# SpeedoMetr.net
KiCad netlist of a schematic drawn in Altium Designer
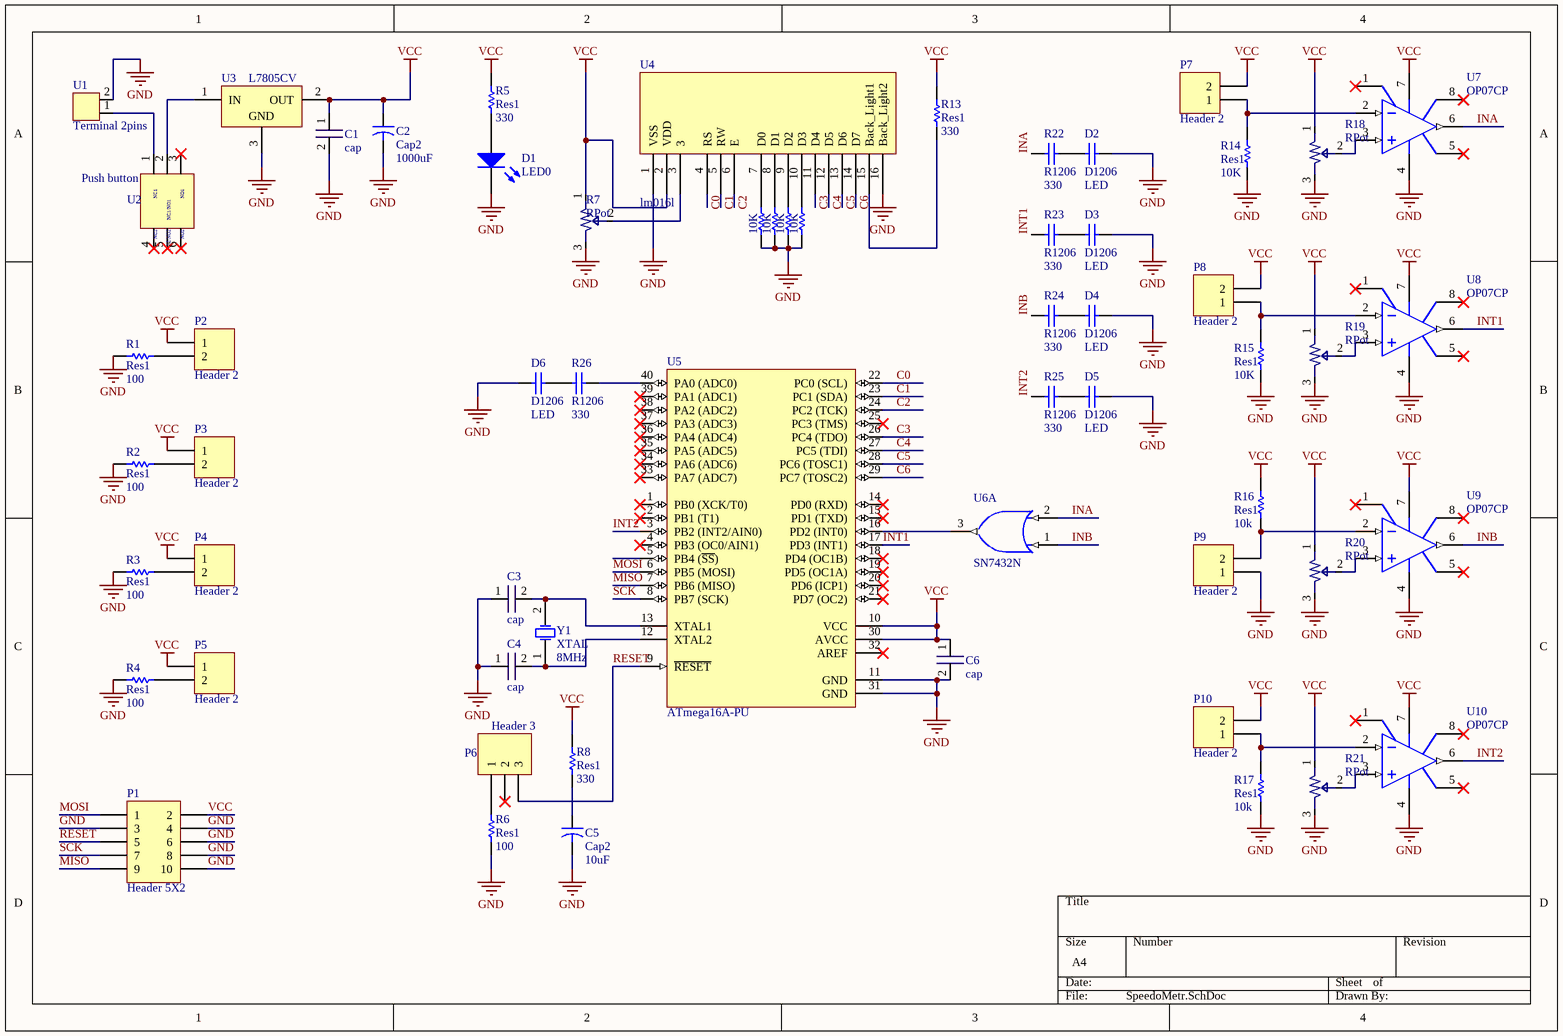
[diagram p0: SpeedoMetr.SchDoc]

(export (version "E")
  (design (tool "Eeschema 10.0.6"))
  (components
    (comp (ref "C1") (value "cap") (footprint "cap 104") (libsource (lib "cap 104") (part "cap 104")))
    (comp (ref "C2")
      (value "Cap2")
      (footprint "RB")
      (description "Capacitor")
      (fields (field (name "ALTIUM_VALUE") "1000uF") (field (name "PUBLISHER") "Altium Limited"))
      (libsource (lib "Miscellaneous Devices") (part "Cap2"))
    )
    (comp (ref "C3") (value "cap") (footprint "cap 104") (libsource (lib "cap 104") (part "cap 104")))
    (comp (ref "C4") (value "cap") (footprint "cap 104") (libsource (lib "cap 104") (part "cap 104")))
    (comp (ref "C5")
      (value "Cap2")
      (footprint "CAPPR5-5x5")
      (description "Capacitor")
      (fields (field (name "ALTIUM_VALUE") "10uF") (field (name "PUBLISHER") "Altium Limited"))
      (libsource (lib "Miscellaneous Devices") (part "Cap2"))
    )
    (comp (ref "C6") (value "cap") (footprint "cap 104") (libsource (lib "cap 104") (part "cap 104")))
    (comp (ref "D1")
      (value "LED0")
      (footprint "LED-0")
      (description "Typical INFRARED GaAs LED")
      (fields (field (name "PUBLISHER") "Altium Limited"))
      (libsource (lib "Miscellaneous Devices") (part "LED0"))
    )
    (comp (ref "D2")
      (value "D1206")
      (footprint "1206")
      (description "Ceramic Chip Capacitor - Standard")
      (fields (field (name "ALTIUM_VALUE") "LED") (field (name "PUBLISHER") "Altium Limited"))
      (libsource (lib "KEMET Chip Capacitor") (part "C1206"))
    )
    (comp (ref "D3")
      (value "D1206")
      (footprint "1206")
      (description "Ceramic Chip Capacitor - Standard")
      (fields (field (name "ALTIUM_VALUE") "LED") (field (name "PUBLISHER") "Altium Limited"))
      (libsource (lib "KEMET Chip Capacitor") (part "C1206"))
    )
    (comp (ref "D4")
      (value "D1206")
      (footprint "1206")
      (description "Ceramic Chip Capacitor - Standard")
      (fields (field (name "ALTIUM_VALUE") "LED") (field (name "PUBLISHER") "Altium Limited"))
      (libsource (lib "KEMET Chip Capacitor") (part "C1206"))
    )
    (comp (ref "D5")
      (value "D1206")
      (footprint "1206")
      (description "Ceramic Chip Capacitor - Standard")
      (fields (field (name "ALTIUM_VALUE") "LED") (field (name "PUBLISHER") "Altium Limited"))
      (libsource (lib "KEMET Chip Capacitor") (part "C1206"))
    )
    (comp (ref "D6")
      (value "D1206")
      (footprint "1206")
      (description "Ceramic Chip Capacitor - Standard")
      (fields (field (name "ALTIUM_VALUE") "LED") (field (name "PUBLISHER") "Altium Limited"))
      (libsource (lib "KEMET Chip Capacitor") (part "C1206"))
    )
    (comp (ref "P1")
      (value "Header 5X2")
      (footprint "HDR2X5")
      (description "Header, 5-Pin, Dual row")
      (fields (field (name "PUBLISHER") "Altium Limited"))
      (libsource (lib "Miscellaneous Connectors") (part "Header 5X2"))
    )
    (comp (ref "P2")
      (value "Header 2")
      (footprint "HDR1X2")
      (description "Header, 2-Pin")
      (fields (field (name "PUBLISHER") "Altium Limited"))
      (libsource (lib "") (part "Header 2_1"))
    )
    (comp (ref "P3")
      (value "Header 2")
      (footprint "HDR1X2")
      (description "Header, 2-Pin")
      (fields (field (name "PUBLISHER") "Altium Limited"))
      (libsource (lib "") (part "Header 2_1"))
    )
    (comp (ref "P4")
      (value "Header 2")
      (footprint "HDR1X2")
      (description "Header, 2-Pin")
      (fields (field (name "PUBLISHER") "Altium Limited"))
      (libsource (lib "") (part "Header 2_1"))
    )
    (comp (ref "P5")
      (value "Header 2")
      (footprint "HDR1X2")
      (description "Header, 2-Pin")
      (fields (field (name "PUBLISHER") "Altium Limited"))
      (libsource (lib "") (part "Header 2_1"))
    )
    (comp (ref "P6")
      (value "Header 3")
      (footprint "HDR1X3")
      (description "Header, 3-Pin")
      (fields (field (name "PUBLISHER") "Altium Limited"))
      (libsource (lib "Miscellaneous Connectors") (part "Header 3"))
    )
    (comp (ref "P7")
      (value "Header 2")
      (footprint "HDR1X2")
      (description "Header, 2-Pin")
      (fields (field (name "PUBLISHER") "Altium Limited"))
      (libsource (lib "Miscellaneous Connectors") (part "Header 2"))
    )
    (comp (ref "P8")
      (value "Header 2")
      (footprint "HDR1X2")
      (description "Header, 2-Pin")
      (fields (field (name "PUBLISHER") "Altium Limited"))
      (libsource (lib "Miscellaneous Connectors") (part "Header 2"))
    )
    (comp (ref "P9")
      (value "Header 2")
      (footprint "HDR1X2")
      (description "Header, 2-Pin")
      (fields (field (name "PUBLISHER") "Altium Limited"))
      (libsource (lib "Miscellaneous Connectors") (part "Header 2"))
    )
    (comp (ref "P10")
      (value "Header 2")
      (footprint "HDR1X2")
      (description "Header, 2-Pin")
      (fields (field (name "PUBLISHER") "Altium Limited"))
      (libsource (lib "Miscellaneous Connectors") (part "Header 2"))
    )
    (comp (ref "R1")
      (value "Res1")
      (footprint "AXIAL-0.3")
      (description "Resistor")
      (fields (field (name "ALTIUM_VALUE") "100") (field (name "PUBLISHER") "Altium Limited"))
      (libsource (lib "Miscellaneous Devices") (part "Res1"))
    )
    (comp (ref "R2")
      (value "Res1")
      (footprint "AXIAL-0.3")
      (description "Resistor")
      (fields (field (name "ALTIUM_VALUE") "100") (field (name "PUBLISHER") "Altium Limited"))
      (libsource (lib "Miscellaneous Devices") (part "Res1"))
    )
    (comp (ref "R3")
      (value "Res1")
      (footprint "AXIAL-0.3")
      (description "Resistor")
      (fields (field (name "ALTIUM_VALUE") "100") (field (name "PUBLISHER") "Altium Limited"))
      (libsource (lib "Miscellaneous Devices") (part "Res1"))
    )
    (comp (ref "R4")
      (value "Res1")
      (footprint "AXIAL-0.3")
      (description "Resistor")
      (fields (field (name "ALTIUM_VALUE") "100") (field (name "PUBLISHER") "Altium Limited"))
      (libsource (lib "Miscellaneous Devices") (part "Res1"))
    )
    (comp (ref "R5")
      (value "Res1")
      (footprint "AXIAL-0.3")
      (description "Resistor")
      (fields (field (name "ALTIUM_VALUE") "330") (field (name "PUBLISHER") "Altium Limited"))
      (libsource (lib "Miscellaneous Devices") (part "Res1"))
    )
    (comp (ref "R6")
      (value "Res1")
      (footprint "AXIAL-0.3")
      (description "Resistor")
      (fields (field (name "ALTIUM_VALUE") "100") (field (name "PUBLISHER") "Altium Limited"))
      (libsource (lib "Miscellaneous Devices") (part "Res1"))
    )
    (comp (ref "R7")
      (value "RPot")
      (footprint "PCBComponent_1")
      (description "Potentiometer")
      (libsource (lib "POT-Blue") (part "Component_1"))
    )
    (comp (ref "R8")
      (value "Res1")
      (footprint "AXIAL-0.3")
      (description "Resistor")
      (fields (field (name "ALTIUM_VALUE") "330") (field (name "PUBLISHER") "Altium Limited"))
      (libsource (lib "Miscellaneous Devices") (part "Res1"))
    )
    (comp (ref "R9")
      (value "10K")
      (footprint "AXIAL-0.3")
      (description "Resistor")
      (fields (field (name "Comment") "Res1") (field (name "PUBLISHER") "Altium Limited"))
      (libsource (lib "Miscellaneous Devices") (part "Res1"))
    )
    (comp (ref "R10")
      (value "10K")
      (footprint "AXIAL-0.3")
      (description "Resistor")
      (fields (field (name "Comment") "Res1") (field (name "PUBLISHER") "Altium Limited"))
      (libsource (lib "Miscellaneous Devices") (part "Res1"))
    )
    (comp (ref "R11")
      (value "10K")
      (footprint "AXIAL-0.3")
      (description "Resistor")
      (fields (field (name "Comment") "Res1") (field (name "PUBLISHER") "Altium Limited"))
      (libsource (lib "Miscellaneous Devices") (part "Res1"))
    )
    (comp (ref "R12")
      (value "10K")
      (footprint "AXIAL-0.3")
      (description "Resistor")
      (fields (field (name "Comment") "Res1") (field (name "PUBLISHER") "Altium Limited"))
      (libsource (lib "Miscellaneous Devices") (part "Res1"))
    )
    (comp (ref "R13")
      (value "Res1")
      (footprint "AXIAL-0.3")
      (description "Resistor")
      (fields (field (name "ALTIUM_VALUE") "330") (field (name "PUBLISHER") "Altium Limited"))
      (libsource (lib "Miscellaneous Devices") (part "Res1"))
    )
    (comp (ref "R14")
      (value "Res1")
      (footprint "AXIAL-0.3")
      (description "Resistor")
      (fields (field (name "ALTIUM_VALUE") "10K") (field (name "PUBLISHER") "Altium Limited"))
      (libsource (lib "Miscellaneous Devices") (part "Res1"))
    )
    (comp (ref "R15")
      (value "Res1")
      (footprint "AXIAL-0.3")
      (description "Resistor")
      (fields (field (name "ALTIUM_VALUE") "10K") (field (name "PUBLISHER") "Altium Limited"))
      (libsource (lib "Miscellaneous Devices") (part "Res1"))
    )
    (comp (ref "R16")
      (value "Res1")
      (footprint "AXIAL-0.3")
      (description "Resistor")
      (fields (field (name "ALTIUM_VALUE") "10k") (field (name "PUBLISHER") "Altium Limited"))
      (libsource (lib "Miscellaneous Devices") (part "Res1"))
    )
    (comp (ref "R17")
      (value "Res1")
      (footprint "AXIAL-0.3")
      (description "Resistor")
      (fields (field (name "ALTIUM_VALUE") "10k") (field (name "PUBLISHER") "Altium Limited"))
      (libsource (lib "Miscellaneous Devices") (part "Res1"))
    )
    (comp (ref "R18")
      (value "RPot")
      (footprint "PCBComponent_1")
      (description "Potentiometer")
      (libsource (lib "POT-Blue") (part "Component_1"))
    )
    (comp (ref "R19")
      (value "RPot")
      (footprint "PCBComponent_1")
      (description "Potentiometer")
      (libsource (lib "POT-Blue") (part "Component_1"))
    )
    (comp (ref "R20")
      (value "RPot")
      (footprint "PCBComponent_1")
      (description "Potentiometer")
      (libsource (lib "POT-Blue") (part "Component_1"))
    )
    (comp (ref "R21")
      (value "RPot")
      (footprint "PCBComponent_1")
      (description "Potentiometer")
      (libsource (lib "POT-Blue") (part "Component_1"))
    )
    (comp (ref "R22")
      (value "R1206")
      (footprint "1206")
      (description "Ceramic Chip Capacitor - Standard")
      (fields (field (name "ALTIUM_VALUE") "330") (field (name "PUBLISHER") "Altium Limited"))
      (libsource (lib "KEMET Chip Capacitor") (part "C1206"))
    )
    (comp (ref "R23")
      (value "R1206")
      (footprint "1206")
      (description "Ceramic Chip Capacitor - Standard")
      (fields (field (name "ALTIUM_VALUE") "330") (field (name "PUBLISHER") "Altium Limited"))
      (libsource (lib "KEMET Chip Capacitor") (part "C1206"))
    )
    (comp (ref "R24")
      (value "R1206")
      (footprint "1206")
      (description "Ceramic Chip Capacitor - Standard")
      (fields (field (name "ALTIUM_VALUE") "330") (field (name "PUBLISHER") "Altium Limited"))
      (libsource (lib "KEMET Chip Capacitor") (part "C1206"))
    )
    (comp (ref "R25")
      (value "R1206")
      (footprint "1206")
      (description "Ceramic Chip Capacitor - Standard")
      (fields (field (name "ALTIUM_VALUE") "330") (field (name "PUBLISHER") "Altium Limited"))
      (libsource (lib "KEMET Chip Capacitor") (part "C1206"))
    )
    (comp (ref "R26")
      (value "R1206")
      (footprint "1206")
      (description "Ceramic Chip Capacitor - Standard")
      (fields (field (name "ALTIUM_VALUE") "330") (field (name "PUBLISHER") "Altium Limited"))
      (libsource (lib "KEMET Chip Capacitor") (part "C1206"))
    )
    (comp (ref "U1")
      (value "Terminal 2pins")
      (footprint "Terminal 2pins")
      (libsource (lib "Terminal 2pins") (part "Terminal"))
    )
    (comp (ref "U2")
      (value "Push button")
      (footprint "PCBComponent_1")
      (description "button")
      (libsource (lib "Push button 6 pin") (part "Component_1"))
    )
    (comp (ref "U3")
      (value "L7805CV")
      (footprint "TO220ABN")
      (description "Positive Voltage Regulator")
      (fields (field (name "PUBLISHER") "Altium Limited"))
      (libsource (lib "ST Power Mgt Voltage Regulator") (part "L7805CV"))
    )
    (comp (ref "U4")
      (value "lm016l")
      (footprint "PCBComponent_1")
      (description "LCD display")
      (libsource (lib "LCD16x2") (part "lm016l"))
    )
    (comp (ref "U5")
      (value "ATmega16A-PU")
      (footprint "40P6")
      (fields (field (name "PUBLISHER") "Altium Limited"))
      (libsource (lib "Atmel Microcontroller 8-Bit megaAVR") (part "ATmega16A-PU"))
    )
    (comp (ref "U6")
      (value "SN7432N")
      (footprint "N014")
      (description "Quadruple 2-Input Positive-OR Gate")
      (fields (field (name "PUBLISHER") "Altium Limited"))
      (libsource (lib "TI Logic Gate 1") (part "SN7432N"))
    )
    (comp (ref "U7")
      (value "OP07CP")
      (footprint "N-8_A")
      (description "Ultra-Low Offset Voltage Operational Amplifier")
      (fields (field (name "PUBLISHER") "Altium Limited"))
      (libsource (lib "AD Operational Amplifier") (part "OP07CP"))
    )
    (comp (ref "U8")
      (value "OP07CP")
      (footprint "N-8_A")
      (description "Ultra-Low Offset Voltage Operational Amplifier")
      (fields (field (name "PUBLISHER") "Altium Limited"))
      (libsource (lib "AD Operational Amplifier") (part "OP07CP"))
    )
    (comp (ref "U9")
      (value "OP07CP")
      (footprint "N-8_A")
      (description "Ultra-Low Offset Voltage Operational Amplifier")
      (fields (field (name "PUBLISHER") "Altium Limited"))
      (libsource (lib "AD Operational Amplifier") (part "OP07CP"))
    )
    (comp (ref "U10")
      (value "OP07CP")
      (footprint "N-8_A")
      (description "Ultra-Low Offset Voltage Operational Amplifier")
      (fields (field (name "PUBLISHER") "Altium Limited"))
      (libsource (lib "AD Operational Amplifier") (part "OP07CP"))
    )
    (comp (ref "Y1")
      (value "XTAL")
      (footprint "XTAL")
      (description "Crystal Oscillator")
      (fields
        (field (name "ALTIUM_VALUE") "8MHz")
        (field (name "DESIGNER") "Meysam Parvizi")
        (field (name "EMAIL") "meysam.parvizi.ir@gmail.com")
      )
      (libsource (lib "mp") (part "XTAL"))
    )
  )
  (nets
    (net (code "1") (name "/C0") (class "Default")
      (node (ref "U4") (pin "4") (pinfunction "RS_4") (pintype "passive"))
      (node (ref "U5") (pin "22") (pinfunction "PC0_(SCL)_22") (pintype "bidirectional"))
    )
    (net (code "2") (name "/C1") (class "Default")
      (node (ref "U4") (pin "5") (pinfunction "RW_5") (pintype "passive"))
      (node (ref "U5") (pin "23") (pinfunction "PC1_(SDA)_23") (pintype "bidirectional"))
    )
    (net (code "3") (name "/C2") (class "Default")
      (node (ref "U4") (pin "6") (pinfunction "E_6") (pintype "passive"))
      (node (ref "U5") (pin "24") (pinfunction "PC2_(TCK)_24") (pintype "bidirectional"))
    )
    (net (code "4") (name "/C3") (class "Default")
      (node (ref "U4") (pin "11") (pinfunction "D4_11") (pintype "passive"))
      (node (ref "U5") (pin "26") (pinfunction "PC4_(TDO)_26") (pintype "bidirectional"))
    )
    (net (code "5") (name "/C4") (class "Default")
      (node (ref "U4") (pin "12") (pinfunction "D5_12") (pintype "passive"))
      (node (ref "U5") (pin "27") (pinfunction "PC5_(TDI)_27") (pintype "bidirectional"))
    )
    (net (code "6") (name "/C5") (class "Default")
      (node (ref "U4") (pin "13") (pinfunction "D6_13") (pintype "passive"))
      (node (ref "U5") (pin "28") (pinfunction "PC6_(TOSC1)_28") (pintype "bidirectional"))
    )
    (net (code "7") (name "/C6") (class "Default")
      (node (ref "U4") (pin "14") (pinfunction "D7_14") (pintype "passive"))
      (node (ref "U5") (pin "29") (pinfunction "PC7_(TOSC2)_29") (pintype "bidirectional"))
    )
    (net (code "8") (name "/INA") (class "Default")
      (node (ref "R22") (pin "1") (pinfunction "1_1") (pintype "passive"))
      (node (ref "U6") (pin "2") (pinfunction "B_2") (pintype "input"))
      (node (ref "U7") (pin "6") (pinfunction "OUT_6") (pintype "output"))
    )
    (net (code "9") (name "/INB") (class "Default")
      (node (ref "R24") (pin "1") (pinfunction "1_1") (pintype "passive"))
      (node (ref "U6") (pin "1") (pinfunction "A_1") (pintype "input"))
      (node (ref "U9") (pin "6") (pinfunction "OUT_6") (pintype "output"))
    )
    (net (code "10") (name "/INT1") (class "Default")
      (node (ref "R23") (pin "1") (pinfunction "1_1") (pintype "passive"))
      (node (ref "U5") (pin "17") (pinfunction "PD3_(INT1)_17") (pintype "bidirectional"))
      (node (ref "U8") (pin "6") (pinfunction "OUT_6") (pintype "output"))
    )
    (net (code "11") (name "/INT2") (class "Default")
      (node (ref "R25") (pin "1") (pinfunction "1_1") (pintype "passive"))
      (node (ref "U10") (pin "6") (pinfunction "OUT_6") (pintype "output"))
      (node (ref "U5") (pin "3") (pinfunction "PB2_(INT2/AIN0)_3") (pintype "bidirectional"))
    )
    (net (code "12") (name "/MISO") (class "Default")
      (node (ref "P1") (pin "9") (pinfunction "9_9") (pintype "passive"))
      (node (ref "U5") (pin "7") (pinfunction "PB6_(MISO)_7") (pintype "bidirectional"))
    )
    (net (code "13") (name "/MOSI") (class "Default")
      (node (ref "P1") (pin "1") (pinfunction "1_1") (pintype "passive"))
      (node (ref "U5") (pin "6") (pinfunction "PB5_(MOSI)_6") (pintype "bidirectional"))
    )
    (net (code "14") (name "/RESET") (class "Default")
      (node (ref "P1") (pin "5") (pinfunction "5_5") (pintype "passive"))
      (node (ref "P6") (pin "3") (pinfunction "3_3") (pintype "passive"))
      (node (ref "U5") (pin "9") (pinfunction "~{RESET}_9") (pintype "input"))
    )
    (net (code "15") (name "/SCK") (class "Default")
      (node (ref "P1") (pin "7") (pinfunction "7_7") (pintype "passive"))
      (node (ref "U5") (pin "8") (pinfunction "PB7_(SCK)_8") (pintype "bidirectional"))
    )
    (net (code "16") (name "GND") (class "Default")
      (node (ref "C1") (pin "2") (pinfunction "2_2") (pintype "passive"))
      (node (ref "C2") (pin "2") (pinfunction "2_2") (pintype "passive"))
      (node (ref "C3") (pin "1") (pinfunction "1_1") (pintype "passive"))
      (node (ref "C4") (pin "1") (pinfunction "1_1") (pintype "passive"))
      (node (ref "C5") (pin "2") (pinfunction "2_2") (pintype "passive"))
      (node (ref "C6") (pin "2") (pinfunction "2_2") (pintype "passive"))
      (node (ref "D1") (pin "2") (pinfunction "K_2") (pintype "passive"))
      (node (ref "D2") (pin "2") (pinfunction "2_2") (pintype "passive"))
      (node (ref "D3") (pin "2") (pinfunction "2_2") (pintype "passive"))
      (node (ref "D4") (pin "2") (pinfunction "2_2") (pintype "passive"))
      (node (ref "D5") (pin "2") (pinfunction "2_2") (pintype "passive"))
      (node (ref "D6") (pin "2") (pinfunction "2_2") (pintype "passive"))
      (node (ref "P1") (pin "10") (pinfunction "10_10") (pintype "passive"))
      (node (ref "P1") (pin "3") (pinfunction "3_3") (pintype "passive"))
      (node (ref "P1") (pin "4") (pinfunction "4_4") (pintype "passive"))
      (node (ref "P1") (pin "6") (pinfunction "6_6") (pintype "passive"))
      (node (ref "P1") (pin "8") (pinfunction "8_8") (pintype "passive"))
      (node (ref "P9") (pin "1") (pinfunction "1_1") (pintype "passive"))
      (node (ref "R1") (pin "1") (pinfunction "1_1") (pintype "passive"))
      (node (ref "R10") (pin "1") (pinfunction "1_1") (pintype "passive"))
      (node (ref "R11") (pin "1") (pinfunction "1_1") (pintype "passive"))
      (node (ref "R12") (pin "1") (pinfunction "1_1") (pintype "passive"))
      (node (ref "R14") (pin "1") (pinfunction "1_1") (pintype "passive"))
      (node (ref "R15") (pin "1") (pinfunction "1_1") (pintype "passive"))
      (node (ref "R17") (pin "1") (pinfunction "1_1") (pintype "passive"))
      (node (ref "R18") (pin "3") (pinfunction "3_3") (pintype "passive"))
      (node (ref "R19") (pin "3") (pinfunction "3_3") (pintype "passive"))
      (node (ref "R2") (pin "1") (pinfunction "1_1") (pintype "passive"))
      (node (ref "R20") (pin "3") (pinfunction "3_3") (pintype "passive"))
      (node (ref "R21") (pin "3") (pinfunction "3_3") (pintype "passive"))
      (node (ref "R3") (pin "1") (pinfunction "1_1") (pintype "passive"))
      (node (ref "R4") (pin "1") (pinfunction "1_1") (pintype "passive"))
      (node (ref "R6") (pin "1") (pinfunction "1_1") (pintype "passive"))
      (node (ref "R7") (pin "3") (pinfunction "3_3") (pintype "passive"))
      (node (ref "R9") (pin "1") (pinfunction "1_1") (pintype "passive"))
      (node (ref "U1") (pin "2") (pinfunction "2_2") (pintype "passive"))
      (node (ref "U10") (pin "4") (pinfunction "V-_4") (pintype "power_in"))
      (node (ref "U3") (pin "3") (pinfunction "GND_3") (pintype "power_in"))
      (node (ref "U4") (pin "1") (pinfunction "VSS_1") (pintype "passive"))
      (node (ref "U4") (pin "16") (pinfunction "Back_Light2_16") (pintype "passive"))
      (node (ref "U5") (pin "11") (pinfunction "GND_11") (pintype "power_in"))
      (node (ref "U5") (pin "31") (pinfunction "GND_31") (pintype "power_in"))
      (node (ref "U6") (pin "7") (pinfunction "GND_7") (pintype "power_in"))
      (node (ref "U7") (pin "4") (pinfunction "V-_4") (pintype "power_in"))
      (node (ref "U8") (pin "4") (pinfunction "V-_4") (pintype "power_in"))
      (node (ref "U9") (pin "4") (pinfunction "V-_4") (pintype "power_in"))
    )
    (net (code "17") (name "Net-(C5-Pad1)") (class "Default")
      (node (ref "C5") (pin "1") (pinfunction "1_1") (pintype "passive"))
      (node (ref "R8") (pin "1") (pinfunction "1_1") (pintype "passive"))
    )
    (net (code "18") (name "Net-(D1-A)") (class "Default")
      (node (ref "D1") (pin "1") (pinfunction "A_1") (pintype "passive"))
      (node (ref "R5") (pin "2") (pinfunction "2_2") (pintype "passive"))
    )
    (net (code "19") (name "Net-(D2-Pad1)") (class "Default")
      (node (ref "D2") (pin "1") (pinfunction "1_1") (pintype "passive"))
      (node (ref "R22") (pin "2") (pinfunction "2_2") (pintype "passive"))
    )
    (net (code "20") (name "Net-(D3-Pad1)") (class "Default")
      (node (ref "D3") (pin "1") (pinfunction "1_1") (pintype "passive"))
      (node (ref "R23") (pin "2") (pinfunction "2_2") (pintype "passive"))
    )
    (net (code "21") (name "Net-(D4-Pad1)") (class "Default")
      (node (ref "D4") (pin "1") (pinfunction "1_1") (pintype "passive"))
      (node (ref "R24") (pin "2") (pinfunction "2_2") (pintype "passive"))
    )
    (net (code "22") (name "Net-(D5-Pad1)") (class "Default")
      (node (ref "D5") (pin "1") (pinfunction "1_1") (pintype "passive"))
      (node (ref "R25") (pin "2") (pinfunction "2_2") (pintype "passive"))
    )
    (net (code "23") (name "Net-(D6-Pad1)") (class "Default")
      (node (ref "D6") (pin "1") (pinfunction "1_1") (pintype "passive"))
      (node (ref "R26") (pin "2") (pinfunction "2_2") (pintype "passive"))
    )
    (net (code "24") (name "Net-(P2-Pad2)") (class "Default")
      (node (ref "P2") (pin "2") (pinfunction "2_2") (pintype "passive"))
      (node (ref "R1") (pin "2") (pinfunction "2_2") (pintype "passive"))
    )
    (net (code "25") (name "Net-(P3-Pad2)") (class "Default")
      (node (ref "P3") (pin "2") (pinfunction "2_2") (pintype "passive"))
      (node (ref "R2") (pin "2") (pinfunction "2_2") (pintype "passive"))
    )
    (net (code "26") (name "Net-(P4-Pad2)") (class "Default")
      (node (ref "P4") (pin "2") (pinfunction "2_2") (pintype "passive"))
      (node (ref "R3") (pin "2") (pinfunction "2_2") (pintype "passive"))
    )
    (net (code "27") (name "Net-(P5-Pad2)") (class "Default")
      (node (ref "P5") (pin "2") (pinfunction "2_2") (pintype "passive"))
      (node (ref "R4") (pin "2") (pinfunction "2_2") (pintype "passive"))
    )
    (net (code "28") (name "Net-(P6-Pad1)") (class "Default")
      (node (ref "P6") (pin "1") (pinfunction "1_1") (pintype "passive"))
      (node (ref "R6") (pin "2") (pinfunction "2_2") (pintype "passive"))
    )
    (net (code "29") (name "Net-(R7-Pad2)") (class "Default")
      (node (ref "R7") (pin "2") (pinfunction "2_2") (pintype "passive"))
      (node (ref "U4") (pin "3") (pinfunction "3_3") (pintype "passive"))
    )
    (net (code "30") (name "Net-(U1-Pad1)") (class "Default")
      (node (ref "U1") (pin "1") (pinfunction "1_1") (pintype "passive"))
      (node (ref "U2") (pin "1") (pinfunction "1_1") (pintype "passive"))
    )
    (net (code "31") (name "Net-(U3-IN)") (class "Default")
      (node (ref "U2") (pin "2") (pinfunction "2_2") (pintype "passive"))
      (node (ref "U3") (pin "1") (pinfunction "IN_1") (pintype "power_in"))
    )
    (net (code "32") (name "Net-(U4-Back_Light1)") (class "Default")
      (node (ref "R13") (pin "2") (pinfunction "2_2") (pintype "passive"))
      (node (ref "U4") (pin "15") (pinfunction "Back_Light1_15") (pintype "passive"))
    )
    (net (code "33") (name "Net-(U4-D0)") (class "Default")
      (node (ref "R9") (pin "2") (pinfunction "2_2") (pintype "passive"))
      (node (ref "U4") (pin "7") (pinfunction "D0_7") (pintype "passive"))
    )
    (net (code "34") (name "Net-(U4-D1)") (class "Default")
      (node (ref "R10") (pin "2") (pinfunction "2_2") (pintype "passive"))
      (node (ref "U4") (pin "8") (pinfunction "D1_8") (pintype "passive"))
    )
    (net (code "35") (name "Net-(U4-D2)") (class "Default")
      (node (ref "R11") (pin "2") (pinfunction "2_2") (pintype "passive"))
      (node (ref "U4") (pin "9") (pinfunction "D2_9") (pintype "passive"))
    )
    (net (code "36") (name "Net-(U4-D3)") (class "Default")
      (node (ref "R12") (pin "2") (pinfunction "2_2") (pintype "passive"))
      (node (ref "U4") (pin "10") (pinfunction "D3_10") (pintype "passive"))
    )
    (net (code "37") (name "Net-(U5-PA0_(ADC0))") (class "Default")
      (node (ref "R26") (pin "1") (pinfunction "1_1") (pintype "passive"))
      (node (ref "U5") (pin "40") (pinfunction "PA0_(ADC0)_40") (pintype "bidirectional"))
    )
    (net (code "38") (name "Net-(U5-PD2_(INT0))") (class "Default")
      (node (ref "U5") (pin "16") (pinfunction "PD2_(INT0)_16") (pintype "bidirectional"))
      (node (ref "U6") (pin "3") (pinfunction "Y_3") (pintype "output"))
    )
    (net (code "39") (name "Net-(U5-XTAL1)") (class "Default")
      (node (ref "C3") (pin "2") (pinfunction "2_2") (pintype "passive"))
      (node (ref "U5") (pin "13") (pinfunction "XTAL1_13") (pintype "passive"))
      (node (ref "Y1") (pin "2") (pinfunction "OSC2_2") (pintype "passive"))
    )
    (net (code "40") (name "Net-(U5-XTAL2)") (class "Default")
      (node (ref "C4") (pin "2") (pinfunction "2_2") (pintype "passive"))
      (node (ref "U5") (pin "12") (pinfunction "XTAL2_12") (pintype "passive"))
      (node (ref "Y1") (pin "1") (pinfunction "OSC1_1") (pintype "passive"))
    )
    (net (code "41") (name "Net-(U7-IN+)") (class "Default")
      (node (ref "R18") (pin "2") (pinfunction "2_2") (pintype "passive"))
      (node (ref "U7") (pin "3") (pinfunction "IN+_3") (pintype "input"))
    )
    (net (code "42") (name "Net-(U7-IN-)") (class "Default")
      (node (ref "P7") (pin "1") (pinfunction "1_1") (pintype "passive"))
      (node (ref "R14") (pin "2") (pinfunction "2_2") (pintype "passive"))
      (node (ref "U7") (pin "2") (pinfunction "IN-_2") (pintype "input"))
    )
    (net (code "43") (name "Net-(U8-IN+)") (class "Default")
      (node (ref "R19") (pin "2") (pinfunction "2_2") (pintype "passive"))
      (node (ref "U8") (pin "3") (pinfunction "IN+_3") (pintype "input"))
    )
    (net (code "44") (name "Net-(U8-IN-)") (class "Default")
      (node (ref "P8") (pin "1") (pinfunction "1_1") (pintype "passive"))
      (node (ref "R15") (pin "2") (pinfunction "2_2") (pintype "passive"))
      (node (ref "U8") (pin "2") (pinfunction "IN-_2") (pintype "input"))
    )
    (net (code "45") (name "Net-(U9-IN+)") (class "Default")
      (node (ref "R20") (pin "2") (pinfunction "2_2") (pintype "passive"))
      (node (ref "U9") (pin "3") (pinfunction "IN+_3") (pintype "input"))
    )
    (net (code "46") (name "Net-(U9-IN-)") (class "Default")
      (node (ref "P9") (pin "2") (pinfunction "2_2") (pintype "passive"))
      (node (ref "R16") (pin "1") (pinfunction "1_1") (pintype "passive"))
      (node (ref "U9") (pin "2") (pinfunction "IN-_2") (pintype "input"))
    )
    (net (code "47") (name "Net-(U10-IN+)") (class "Default")
      (node (ref "R21") (pin "2") (pinfunction "2_2") (pintype "passive"))
      (node (ref "U10") (pin "3") (pinfunction "IN+_3") (pintype "input"))
    )
    (net (code "48") (name "Net-(U10-IN-)") (class "Default")
      (node (ref "P10") (pin "1") (pinfunction "1_1") (pintype "passive"))
      (node (ref "R17") (pin "2") (pinfunction "2_2") (pintype "passive"))
      (node (ref "U10") (pin "2") (pinfunction "IN-_2") (pintype "input"))
    )
    (net (code "49") (name "VCC") (class "Default")
      (node (ref "C1") (pin "1") (pinfunction "1_1") (pintype "passive"))
      (node (ref "C2") (pin "1") (pinfunction "1_1") (pintype "passive"))
      (node (ref "C6") (pin "1") (pinfunction "1_1") (pintype "passive"))
      (node (ref "P1") (pin "2") (pinfunction "2_2") (pintype "passive"))
      (node (ref "P10") (pin "2") (pinfunction "2_2") (pintype "passive"))
      (node (ref "P2") (pin "1") (pinfunction "1_1") (pintype "passive"))
      (node (ref "P3") (pin "1") (pinfunction "1_1") (pintype "passive"))
      (node (ref "P4") (pin "1") (pinfunction "1_1") (pintype "passive"))
      (node (ref "P5") (pin "1") (pinfunction "1_1") (pintype "passive"))
      (node (ref "P7") (pin "2") (pinfunction "2_2") (pintype "passive"))
      (node (ref "P8") (pin "2") (pinfunction "2_2") (pintype "passive"))
      (node (ref "R13") (pin "1") (pinfunction "1_1") (pintype "passive"))
      (node (ref "R16") (pin "2") (pinfunction "2_2") (pintype "passive"))
      (node (ref "R18") (pin "1") (pinfunction "1_1") (pintype "passive"))
      (node (ref "R19") (pin "1") (pinfunction "1_1") (pintype "passive"))
      (node (ref "R20") (pin "1") (pinfunction "1_1") (pintype "passive"))
      (node (ref "R21") (pin "1") (pinfunction "1_1") (pintype "passive"))
      (node (ref "R5") (pin "1") (pinfunction "1_1") (pintype "passive"))
      (node (ref "R7") (pin "1") (pinfunction "1_1") (pintype "passive"))
      (node (ref "R8") (pin "2") (pinfunction "2_2") (pintype "passive"))
      (node (ref "U10") (pin "7") (pinfunction "V+_7") (pintype "power_in"))
      (node (ref "U3") (pin "2") (pinfunction "OUT_2") (pintype "power_in"))
      (node (ref "U4") (pin "2") (pinfunction "VDD_2") (pintype "passive"))
      (node (ref "U5") (pin "10") (pinfunction "VCC_10") (pintype "power_in"))
      (node (ref "U5") (pin "30") (pinfunction "AVCC_30") (pintype "power_in"))
      (node (ref "U6") (pin "14") (pinfunction "VCC_14") (pintype "power_in"))
      (node (ref "U7") (pin "7") (pinfunction "V+_7") (pintype "power_in"))
      (node (ref "U8") (pin "7") (pinfunction "V+_7") (pintype "power_in"))
      (node (ref "U9") (pin "7") (pinfunction "V+_7") (pintype "power_in"))
    )
    (net (code "50") (name "unconnected-(P6-Pad2)") (class "Default")
      (node (ref "P6") (pin "2") (pinfunction "2_2") (pintype "passive+no_connect"))
    )
    (net (code "51") (name "unconnected-(U2-Pad3)") (class "Default")
      (node (ref "U2") (pin "3") (pinfunction "3_3") (pintype "passive+no_connect"))
    )
    (net (code "52") (name "unconnected-(U2-Pad4)") (class "Default")
      (node (ref "U2") (pin "4") (pinfunction "4_4") (pintype "passive+no_connect"))
    )
    (net (code "53") (name "unconnected-(U2-Pad5)") (class "Default")
      (node (ref "U2") (pin "5") (pinfunction "5_5") (pintype "passive+no_connect"))
    )
    (net (code "54") (name "unconnected-(U2-Pad6)") (class "Default")
      (node (ref "U2") (pin "6") (pinfunction "6_6") (pintype "passive+no_connect"))
    )
    (net (code "55") (name "unconnected-(U5-AREF-Pad32)") (class "Default")
      (node (ref "U5") (pin "32") (pinfunction "AREF_32") (pintype "power_in+no_connect"))
    )
    (net (code "56") (name "unconnected-(U5-PA1_(ADC1)-Pad39)") (class "Default")
      (node (ref "U5") (pin "39") (pinfunction "PA1_(ADC1)_39") (pintype "bidirectional+no_connect"))
    )
    (net (code "57") (name "unconnected-(U5-PA2_(ADC2)-Pad38)") (class "Default")
      (node (ref "U5") (pin "38") (pinfunction "PA2_(ADC2)_38") (pintype "bidirectional+no_connect"))
    )
    (net (code "58") (name "unconnected-(U5-PA3_(ADC3)-Pad37)") (class "Default")
      (node (ref "U5") (pin "37") (pinfunction "PA3_(ADC3)_37") (pintype "bidirectional+no_connect"))
    )
    (net (code "59") (name "unconnected-(U5-PA4_(ADC4)-Pad36)") (class "Default")
      (node (ref "U5") (pin "36") (pinfunction "PA4_(ADC4)_36") (pintype "bidirectional+no_connect"))
    )
    (net (code "60") (name "unconnected-(U5-PA5_(ADC5)-Pad35)") (class "Default")
      (node (ref "U5") (pin "35") (pinfunction "PA5_(ADC5)_35") (pintype "bidirectional+no_connect"))
    )
    (net (code "61") (name "unconnected-(U5-PA6_(ADC6)-Pad34)") (class "Default")
      (node (ref "U5") (pin "34") (pinfunction "PA6_(ADC6)_34") (pintype "bidirectional+no_connect"))
    )
    (net (code "62") (name "unconnected-(U5-PA7_(ADC7)-Pad33)") (class "Default")
      (node (ref "U5") (pin "33") (pinfunction "PA7_(ADC7)_33") (pintype "bidirectional+no_connect"))
    )
    (net (code "63") (name "unconnected-(U5-PB0_(XCK{slash}T0)-Pad1)") (class "Default")
      (node (ref "U5") (pin "1") (pinfunction "PB0_(XCK/T0)_1") (pintype "bidirectional+no_connect"))
    )
    (net (code "64") (name "unconnected-(U5-PB1_(T1)-Pad2)") (class "Default")
      (node (ref "U5") (pin "2") (pinfunction "PB1_(T1)_2") (pintype "bidirectional+no_connect"))
    )
    (net (code "65") (name "unconnected-(U5-PB3_(OC0{slash}AIN1)-Pad4)") (class "Default")
      (node (ref "U5") (pin "4") (pinfunction "PB3_(OC0/AIN1)_4") (pintype "bidirectional+no_connect"))
    )
    (net (code "66") (name "unconnected-(U5-PB4_(~{SS})-Pad5)") (class "Default")
      (node (ref "U5") (pin "5") (pinfunction "PB4_(~{SS})_5") (pintype "bidirectional"))
    )
    (net (code "67") (name "unconnected-(U5-PC3_(TMS)-Pad25)") (class "Default")
      (node (ref "U5") (pin "25") (pinfunction "PC3_(TMS)_25") (pintype "bidirectional+no_connect"))
    )
    (net (code "68") (name "unconnected-(U5-PD0_(RXD)-Pad14)") (class "Default")
      (node (ref "U5") (pin "14") (pinfunction "PD0_(RXD)_14") (pintype "bidirectional+no_connect"))
    )
    (net (code "69") (name "unconnected-(U5-PD1_(TXD)-Pad15)") (class "Default")
      (node (ref "U5") (pin "15") (pinfunction "PD1_(TXD)_15") (pintype "bidirectional+no_connect"))
    )
    (net (code "70") (name "unconnected-(U5-PD4_(OC1B)-Pad18)") (class "Default")
      (node (ref "U5") (pin "18") (pinfunction "PD4_(OC1B)_18") (pintype "bidirectional+no_connect"))
    )
    (net (code "71") (name "unconnected-(U5-PD5_(OC1A)-Pad19)") (class "Default")
      (node (ref "U5") (pin "19") (pinfunction "PD5_(OC1A)_19") (pintype "bidirectional+no_connect"))
    )
    (net (code "72") (name "unconnected-(U5-PD6_(ICP1)-Pad20)") (class "Default")
      (node (ref "U5") (pin "20") (pinfunction "PD6_(ICP1)_20") (pintype "bidirectional+no_connect"))
    )
    (net (code "73") (name "unconnected-(U5-PD7_(OC2)-Pad21)") (class "Default")
      (node (ref "U5") (pin "21") (pinfunction "PD7_(OC2)_21") (pintype "bidirectional+no_connect"))
    )
    (net (code "74") (name "unconnected-(U7-NC-Pad5)") (class "Default")
      (node (ref "U7") (pin "5") (pinfunction "NC_5") (pintype "passive+no_connect"))
    )
    (net (code "75") (name "unconnected-(U7-VOSTRIM-Pad1)") (class "Default")
      (node (ref "U7") (pin "1") (pinfunction "VOSTRIM_1") (pintype "passive+no_connect"))
    )
    (net (code "76") (name "unconnected-(U7-VOSTRIM-Pad8)") (class "Default")
      (node (ref "U7") (pin "8") (pinfunction "VOSTRIM_8") (pintype "passive+no_connect"))
    )
    (net (code "77") (name "unconnected-(U8-NC-Pad5)") (class "Default")
      (node (ref "U8") (pin "5") (pinfunction "NC_5") (pintype "passive+no_connect"))
    )
    (net (code "78") (name "unconnected-(U8-VOSTRIM-Pad1)") (class "Default")
      (node (ref "U8") (pin "1") (pinfunction "VOSTRIM_1") (pintype "passive+no_connect"))
    )
    (net (code "79") (name "unconnected-(U8-VOSTRIM-Pad8)") (class "Default")
      (node (ref "U8") (pin "8") (pinfunction "VOSTRIM_8") (pintype "passive+no_connect"))
    )
    (net (code "80") (name "unconnected-(U9-NC-Pad5)") (class "Default")
      (node (ref "U9") (pin "5") (pinfunction "NC_5") (pintype "passive+no_connect"))
    )
    (net (code "81") (name "unconnected-(U9-VOSTRIM-Pad1)") (class "Default")
      (node (ref "U9") (pin "1") (pinfunction "VOSTRIM_1") (pintype "passive+no_connect"))
    )
    (net (code "82") (name "unconnected-(U9-VOSTRIM-Pad8)") (class "Default")
      (node (ref "U9") (pin "8") (pinfunction "VOSTRIM_8") (pintype "passive+no_connect"))
    )
    (net (code "83") (name "unconnected-(U10-NC-Pad5)") (class "Default")
      (node (ref "U10") (pin "5") (pinfunction "NC_5") (pintype "passive+no_connect"))
    )
    (net (code "84") (name "unconnected-(U10-VOSTRIM-Pad1)") (class "Default")
      (node (ref "U10") (pin "1") (pinfunction "VOSTRIM_1") (pintype "passive+no_connect"))
    )
    (net (code "85") (name "unconnected-(U10-VOSTRIM-Pad8)") (class "Default")
      (node (ref "U10") (pin "8") (pinfunction "VOSTRIM_8") (pintype "passive+no_connect"))
    )
  )
)
